# XenoPreamp.net
KiCad netlist of a schematic drawn in EAGLE
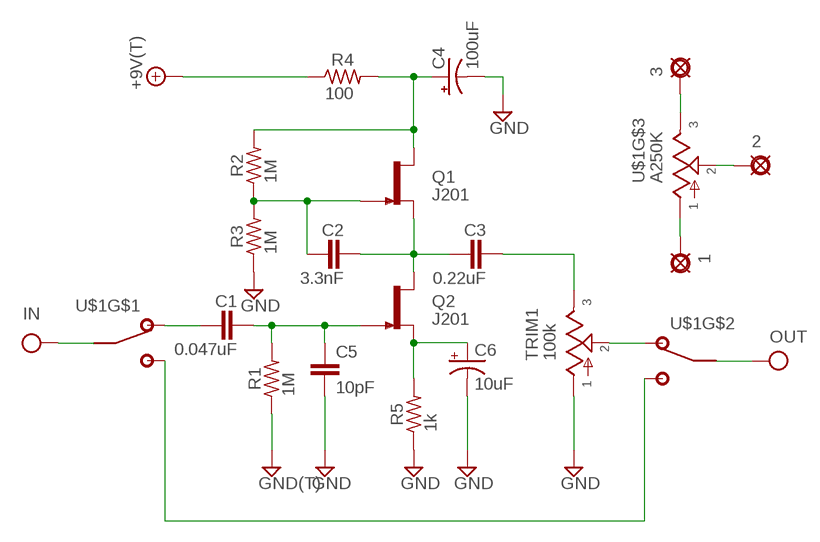
[diagram p0: schematic, sheet 1]

(export (version "E")
  (design (tool "Eeschema 10.0.6"))
  (components
    (comp (ref "+9V")
      (value "+9V(T)")
      (footprint "eagle-import:SQUARE")
      (libsource (lib "eagle-import") (part "+9V(T)"))
    )
    (comp (ref "1")
      (value "VOLIN")
      (footprint "eagle-import:OCTOGON")
      (libsource (lib "eagle-import") (part "PAD8"))
    )
    (comp (ref "2")
      (value "VOLOUT")
      (footprint "eagle-import:OCTOGON")
      (libsource (lib "eagle-import") (part "PAD8"))
    )
    (comp (ref "3")
      (value "GNF")
      (footprint "eagle-import:OCTOGON")
      (libsource (lib "eagle-import") (part "PAD8"))
    )
    (comp (ref "C1")
      (value "0.047uF")
      (footprint "eagle-import:072X025")
      (libsource (lib "eagle-import") (part "072X0252"))
    )
    (comp (ref "C2")
      (value "3.3nF")
      (footprint "eagle-import:072X025")
      (libsource (lib "eagle-import") (part "072X0252"))
    )
    (comp (ref "C3")
      (value "0.22uF")
      (footprint "eagle-import:072X025")
      (libsource (lib "eagle-import") (part "072X0252"))
    )
    (comp (ref "C4")
      (value "100uF")
      (footprint "eagle-import:063_025")
      (libsource (lib "eagle-import") (part "0631"))
    )
    (comp (ref "C5")
      (value "10pF")
      (footprint "eagle-import:050X030_025")
      (libsource (lib "eagle-import") (part "050X030_0251"))
    )
    (comp (ref "C6")
      (value "10uF")
      (footprint "eagle-import:050_020_1")
      (libsource (lib "eagle-import") (part "0501"))
    )
    (comp (ref "GND")
      (value "GND(T)")
      (footprint "eagle-import:SQUARE")
      (libsource (lib "eagle-import") (part "GND(T)"))
    )
    (comp (ref "IN")
      (value "IN(T)")
      (footprint "eagle-import:SQUARE")
      (libsource (lib "eagle-import") (part "IN(T)"))
    )
    (comp (ref "OUT")
      (value "OUT(T)")
      (footprint "eagle-import:SQUARE")
      (libsource (lib "eagle-import") (part "OUT(T)"))
    )
    (comp (ref "Q1")
      (value "J201")
      (footprint "eagle-import:TO92-")
      (libsource (lib "eagle-import") (part "J201"))
    )
    (comp (ref "Q2")
      (value "J201")
      (footprint "eagle-import:TO92-")
      (libsource (lib "eagle-import") (part "J201"))
    )
    (comp (ref "R1")
      (value "1M")
      (footprint "eagle-import:R0207_3")
      (libsource (lib "eagle-import") (part "6MM.3"))
    )
    (comp (ref "R2")
      (value "1M")
      (footprint "eagle-import:R0207_3")
      (libsource (lib "eagle-import") (part "6MM.3"))
    )
    (comp (ref "R3")
      (value "1M")
      (footprint "eagle-import:R0207_3")
      (libsource (lib "eagle-import") (part "6MM.3"))
    )
    (comp (ref "R4")
      (value "100")
      (footprint "eagle-import:R0207_3")
      (libsource (lib "eagle-import") (part "6MM.3"))
    )
    (comp (ref "R5")
      (value "1k")
      (footprint "eagle-import:R0207_3")
      (libsource (lib "eagle-import") (part "6MM.3"))
    )
    (comp (ref "TRIM1")
      (value "100k")
      (footprint "eagle-import:B25P")
      (libsource (lib "eagle-import") (part "POTTRIM"))
    )
    (comp (ref "U$1")
      (value "A250K")
      (footprint "eagle-import:16MM-PCB-MOUNT-DPDT")
      (libsource (lib "eagle-import") (part "16MMDPDT"))
    )
  )
  (nets
    (net (code "1") (name "+9V(T)") (class "Default")
      (node (ref "+9V") (pin "1") (pinfunction "+9V_1") (pintype "power_in"))
      (node (ref "R4") (pin "1") (pinfunction "1_1") (pintype "passive"))
    )
    (net (code "2") (name "GND") (class "Default")
      (node (ref "C4") (pin "-") (pinfunction "-_-") (pintype "passive"))
      (node (ref "C5") (pin "2") (pinfunction "2_2") (pintype "passive"))
      (node (ref "C6") (pin "-") (pinfunction "-_-") (pintype "passive"))
      (node (ref "GND") (pin "1") (pinfunction "GND_1") (pintype "power_in"))
      (node (ref "R1") (pin "1") (pinfunction "1_1") (pintype "passive"))
      (node (ref "R3") (pin "1") (pinfunction "1_1") (pintype "passive"))
      (node (ref "R5") (pin "1") (pinfunction "1_1") (pintype "passive"))
      (node (ref "TRIM1") (pin "1") (pinfunction "1_1") (pintype "passive"))
    )
    (net (code "3") (name "IN(T)") (class "Default")
      (node (ref "IN") (pin "1") (pinfunction "IN_1") (pintype "power_in"))
      (node (ref "U$1") (pin "SA2") (pinfunction "2_SA2") (pintype "passive"))
    )
    (net (code "4") (name "Net-(1-PAD)") (class "Default")
      (node (ref "1") (pin "1") (pinfunction "PAD_1") (pintype "passive"))
      (node (ref "U$1") (pin "1") (pinfunction "1_1") (pintype "passive"))
    )
    (net (code "5") (name "Net-(2-PAD)") (class "Default")
      (node (ref "2") (pin "1") (pinfunction "PAD_1") (pintype "passive"))
      (node (ref "U$1") (pin "2") (pinfunction "2_2") (pintype "passive"))
    )
    (net (code "6") (name "Net-(3-PAD)") (class "Default")
      (node (ref "3") (pin "1") (pinfunction "PAD_1") (pintype "passive"))
      (node (ref "U$1") (pin "3") (pinfunction "3_3") (pintype "passive"))
    )
    (net (code "7") (name "Net-(C3-Pad2)") (class "Default")
      (node (ref "C3") (pin "2") (pinfunction "2_2") (pintype "passive"))
      (node (ref "TRIM1") (pin "3") (pinfunction "3_3") (pintype "passive"))
    )
    (net (code "8") (name "Net-(Q1-D)") (class "Default")
      (node (ref "C4") (pin "+") (pinfunction "+_+") (pintype "passive"))
      (node (ref "Q1") (pin "3") (pinfunction "D_3") (pintype "passive"))
      (node (ref "R2") (pin "2") (pinfunction "2_2") (pintype "passive"))
      (node (ref "R4") (pin "2") (pinfunction "2_2") (pintype "passive"))
    )
    (net (code "9") (name "Net-(Q1-G)") (class "Default")
      (node (ref "C2") (pin "1") (pinfunction "1_1") (pintype "passive"))
      (node (ref "Q1") (pin "1") (pinfunction "G_1") (pintype "passive"))
      (node (ref "R2") (pin "1") (pinfunction "1_1") (pintype "passive"))
      (node (ref "R3") (pin "2") (pinfunction "2_2") (pintype "passive"))
    )
    (net (code "10") (name "Net-(Q1-S)") (class "Default")
      (node (ref "C2") (pin "2") (pinfunction "2_2") (pintype "passive"))
      (node (ref "C3") (pin "1") (pinfunction "1_1") (pintype "passive"))
      (node (ref "Q1") (pin "2") (pinfunction "S_2") (pintype "passive"))
      (node (ref "Q2") (pin "3") (pinfunction "D_3") (pintype "passive"))
    )
    (net (code "11") (name "Net-(Q2-G)") (class "Default")
      (node (ref "C1") (pin "2") (pinfunction "2_2") (pintype "passive"))
      (node (ref "C5") (pin "1") (pinfunction "1_1") (pintype "passive"))
      (node (ref "Q2") (pin "1") (pinfunction "G_1") (pintype "passive"))
      (node (ref "R1") (pin "2") (pinfunction "2_2") (pintype "passive"))
    )
    (net (code "12") (name "Net-(Q2-S)") (class "Default")
      (node (ref "C6") (pin "+") (pinfunction "+_+") (pintype "passive"))
      (node (ref "Q2") (pin "2") (pinfunction "S_2") (pintype "passive"))
      (node (ref "R5") (pin "2") (pinfunction "2_2") (pintype "passive"))
    )
    (net (code "13") (name "Net-(U$1A-1)") (class "Default")
      (node (ref "C1") (pin "1") (pinfunction "1_1") (pintype "passive"))
      (node (ref "U$1") (pin "SA1") (pinfunction "1_SA1") (pintype "passive"))
    )
    (net (code "14") (name "Net-(U$1A-3)") (class "Default")
      (node (ref "U$1") (pin "SA3") (pinfunction "3_SA3") (pintype "passive"))
      (node (ref "U$1") (pin "SB3") (pinfunction "3_SB3") (pintype "passive"))
    )
    (net (code "15") (name "Net-(U$1B-1)") (class "Default")
      (node (ref "TRIM1") (pin "2") (pinfunction "2_2") (pintype "passive"))
      (node (ref "U$1") (pin "SB1") (pinfunction "1_SB1") (pintype "passive"))
    )
    (net (code "16") (name "OUT(T)") (class "Default")
      (node (ref "OUT") (pin "1") (pinfunction "OUT_1") (pintype "power_in"))
      (node (ref "U$1") (pin "SB2") (pinfunction "2_SB2") (pintype "passive"))
    )
  )
)
